# emitter_follower_punto_di_lavoro.net
KiCad netlist of a schematic drawn in EAGLE
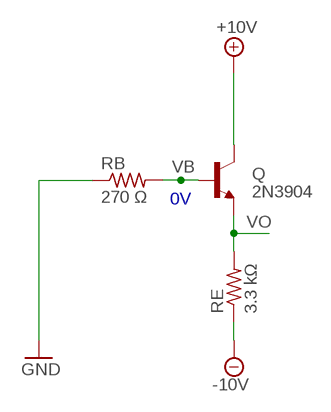
[diagram p0: schematic, sheet 1]

(export (version "E")
  (design (tool "Eeschema 10.0.6"))
  (components
    (comp (ref "Q")
      (value "2N3904")
      (footprint "eagle-import:TO92")
      (libsource (lib "eagle-import") (part "2N3904"))
    )
    (comp (ref "RB")
      (value "270 Ω")
      (footprint "eagle-import:0204_5")
      (libsource (lib "eagle-import") (part "R-US_0204/5"))
    )
    (comp (ref "RE")
      (value "3.3 kΩ")
      (footprint "eagle-import:0204_5")
      (libsource (lib "eagle-import") (part "R-US_0204/5"))
    )
  )
  (nets
    (net (code "1") (name "+10V") (class "Default")
      (node (ref "Q") (pin "1") (pinfunction "C_1") (pintype "passive"))
    )
    (net (code "2") (name "-10V") (class "Default")
      (node (ref "RE") (pin "1") (pinfunction "1_1") (pintype "passive"))
    )
    (net (code "3") (name "/VB") (class "Default")
      (node (ref "Q") (pin "2") (pinfunction "B_2") (pintype "passive"))
      (node (ref "RB") (pin "2") (pinfunction "2_2") (pintype "passive"))
    )
    (net (code "4") (name "/VO") (class "Default")
      (node (ref "Q") (pin "3") (pinfunction "E_3") (pintype "passive"))
      (node (ref "RE") (pin "2") (pinfunction "2_2") (pintype "passive"))
    )
    (net (code "5") (name "GND") (class "Default")
      (node (ref "RB") (pin "1") (pinfunction "1_1") (pintype "passive"))
    )
  )
)
